# TMC2210_V10.net
KiCad netlist of a schematic drawn in Altium Designer
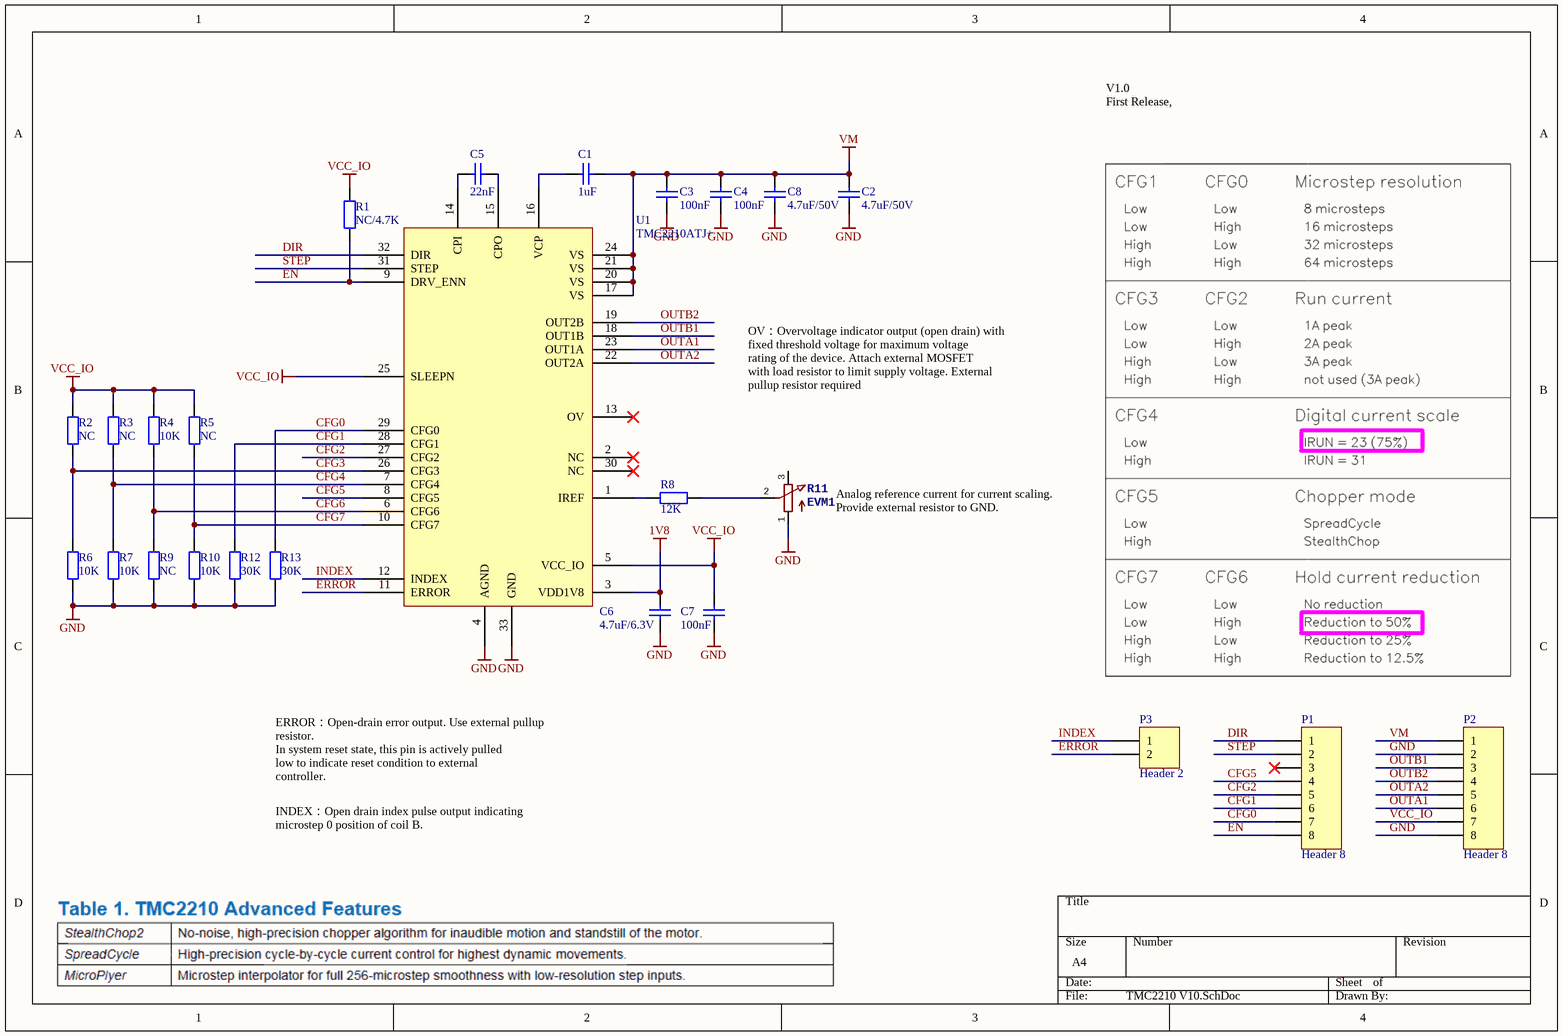
[diagram p0: TMC2210 V10.SchDoc]

(export (version "E")
  (design (tool "Eeschema 10.0.6"))
  (components
    (comp (ref "C1") (value "1uF") (footprint "CAP0402_NS") (libsource (lib "接插件库") (part "Capacitor")))
    (comp (ref "C2") (value "4.7uF/50V") (footprint "CAP0805") (libsource (lib "接插件库") (part "Capacitor")))
    (comp (ref "C3") (value "100nF") (footprint "CAP0402_NS") (libsource (lib "接插件库") (part "Capacitor")))
    (comp (ref "C4") (value "100nF") (footprint "CAP0402_NS") (libsource (lib "接插件库") (part "Capacitor")))
    (comp (ref "C5") (value "22nF") (footprint "CAP0402_NS") (libsource (lib "接插件库") (part "Capacitor")))
    (comp (ref "C6")
      (value "4.7uF/6.3V")
      (footprint "CAP0402_NS")
      (libsource (lib "接插件库") (part "Capacitor"))
    )
    (comp (ref "C7") (value "100nF") (footprint "CAP0402_NS") (libsource (lib "接插件库") (part "Capacitor")))
    (comp (ref "C8") (value "4.7uF/50V") (footprint "CAP0805") (libsource (lib "接插件库") (part "Capacitor")))
    (comp (ref "P1")
      (value "Header 8")
      (footprint "Header 1X8")
      (description "Header, 8-Pin")
      (fields (field (name "PUBLISHER") "Altium Limited"))
      (libsource (lib "Miscellaneous Connectors") (part "Header 8"))
    )
    (comp (ref "P2")
      (value "Header 8")
      (footprint "Header 1X8")
      (description "Header, 8-Pin")
      (fields (field (name "PUBLISHER") "Altium Limited"))
      (libsource (lib "Miscellaneous Connectors") (part "Header 8"))
    )
    (comp (ref "P3")
      (value "Header 2")
      (footprint "HDR1X2")
      (description "Header, 2-Pin")
      (fields (field (name "PUBLISHER") "Altium Limited"))
      (libsource (lib "Miscellaneous Connectors") (part "Header 2"))
    )
    (comp (ref "R1") (value "NC/4.7K") (footprint "RES0402_NS") (libsource (lib "接插件库") (part "Resistor")))
    (comp (ref "R2") (value "NC") (footprint "RES0402_NS") (libsource (lib "接插件库") (part "Resistor")))
    (comp (ref "R3") (value "NC") (footprint "RES0402_NS") (libsource (lib "接插件库") (part "Resistor")))
    (comp (ref "R4") (value "10K") (footprint "RES0402_NS") (libsource (lib "接插件库") (part "Resistor")))
    (comp (ref "R5") (value "NC") (footprint "RES0402_NS") (libsource (lib "接插件库") (part "Resistor")))
    (comp (ref "R6") (value "10K") (footprint "RES0402_NS") (libsource (lib "接插件库") (part "Resistor")))
    (comp (ref "R7") (value "10K") (footprint "RES0402_NS") (libsource (lib "接插件库") (part "Resistor")))
    (comp (ref "R8") (value "12K") (footprint "RES0402") (libsource (lib "") (part "Resistor_1")))
    (comp (ref "R9") (value "NC") (footprint "RES0402_NS") (libsource (lib "接插件库") (part "Resistor")))
    (comp (ref "R10") (value "10K") (footprint "RES0402_NS") (libsource (lib "接插件库") (part "Resistor")))
    (comp (ref "R11")
      (value "EVM1USX30B54")
      (footprint "POT_EVM3R")
      (description "Potentiometer")
      (libsource (lib "we-rcl") (part "POTEVM3R"))
    )
    (comp (ref "R12") (value "30K") (footprint "RES0402_NS") (libsource (lib "接插件库") (part "Resistor")))
    (comp (ref "R13") (value "30K") (footprint "RES0402_NS") (libsource (lib "接插件库") (part "Resistor")))
    (comp (ref "U1")
      (value "TMC2210ATJ+")
      (footprint "QFN32(Atmel)")
      (libsource (lib "接插件库") (part "TMC2210ATJ+"))
    )
  )
  (nets
    (net (code "1") (name "/CFG0") (class "Default")
      (node (ref "P1") (pin "7") (pinfunction "7_7") (pintype "passive"))
      (node (ref "R13") (pin "2") (pinfunction "2_2") (pintype "passive"))
      (node (ref "U1") (pin "29") (pinfunction "CFG0_29") (pintype "passive"))
    )
    (net (code "2") (name "/CFG1") (class "Default")
      (node (ref "P1") (pin "6") (pinfunction "6_6") (pintype "passive"))
      (node (ref "R12") (pin "2") (pinfunction "2_2") (pintype "passive"))
      (node (ref "U1") (pin "28") (pinfunction "CFG1_28") (pintype "passive"))
    )
    (net (code "3") (name "/CFG2") (class "Default")
      (node (ref "P1") (pin "5") (pinfunction "5_5") (pintype "passive"))
      (node (ref "U1") (pin "27") (pinfunction "CFG2_27") (pintype "passive"))
    )
    (net (code "4") (name "/CFG3") (class "Default")
      (node (ref "R2") (pin "1") (pinfunction "1_1") (pintype "passive"))
      (node (ref "R6") (pin "2") (pinfunction "2_2") (pintype "passive"))
      (node (ref "U1") (pin "26") (pinfunction "CFG3_26") (pintype "passive"))
    )
    (net (code "5") (name "/CFG4") (class "Default")
      (node (ref "R3") (pin "1") (pinfunction "1_1") (pintype "passive"))
      (node (ref "R7") (pin "2") (pinfunction "2_2") (pintype "passive"))
      (node (ref "U1") (pin "7") (pinfunction "CFG4_7") (pintype "passive"))
    )
    (net (code "6") (name "/CFG5") (class "Default")
      (node (ref "P1") (pin "4") (pinfunction "4_4") (pintype "passive"))
      (node (ref "U1") (pin "8") (pinfunction "CFG5_8") (pintype "passive"))
    )
    (net (code "7") (name "/CFG6") (class "Default")
      (node (ref "R4") (pin "1") (pinfunction "1_1") (pintype "passive"))
      (node (ref "R9") (pin "2") (pinfunction "2_2") (pintype "passive"))
      (node (ref "U1") (pin "6") (pinfunction "CFG6_6") (pintype "passive"))
    )
    (net (code "8") (name "/CFG7") (class "Default")
      (node (ref "R10") (pin "2") (pinfunction "2_2") (pintype "passive"))
      (node (ref "R5") (pin "1") (pinfunction "1_1") (pintype "passive"))
      (node (ref "U1") (pin "10") (pinfunction "CFG7_10") (pintype "passive"))
    )
    (net (code "9") (name "/DIR") (class "Default")
      (node (ref "P1") (pin "1") (pinfunction "1_1") (pintype "passive"))
      (node (ref "U1") (pin "32") (pinfunction "DIR_32") (pintype "passive"))
    )
    (net (code "10") (name "/EN") (class "Default")
      (node (ref "P1") (pin "8") (pinfunction "8_8") (pintype "passive"))
      (node (ref "R1") (pin "1") (pinfunction "1_1") (pintype "passive"))
      (node (ref "U1") (pin "9") (pinfunction "DRV_ENN_9") (pintype "passive"))
    )
    (net (code "11") (name "/ERROR") (class "Default")
      (node (ref "P3") (pin "2") (pinfunction "2_2") (pintype "passive"))
      (node (ref "U1") (pin "11") (pinfunction "ERROR_11") (pintype "passive"))
    )
    (net (code "12") (name "/INDEX") (class "Default")
      (node (ref "P3") (pin "1") (pinfunction "1_1") (pintype "passive"))
      (node (ref "U1") (pin "12") (pinfunction "INDEX_12") (pintype "passive"))
    )
    (net (code "13") (name "/OUTA1") (class "Default")
      (node (ref "P2") (pin "6") (pinfunction "6_6") (pintype "passive"))
      (node (ref "U1") (pin "23") (pinfunction "OUT1A_23") (pintype "passive"))
    )
    (net (code "14") (name "/OUTA2") (class "Default")
      (node (ref "P2") (pin "5") (pinfunction "5_5") (pintype "passive"))
      (node (ref "U1") (pin "22") (pinfunction "OUT2A_22") (pintype "passive"))
    )
    (net (code "15") (name "/OUTB1") (class "Default")
      (node (ref "P2") (pin "3") (pinfunction "3_3") (pintype "passive"))
      (node (ref "U1") (pin "18") (pinfunction "OUT1B_18") (pintype "passive"))
    )
    (net (code "16") (name "/OUTB2") (class "Default")
      (node (ref "P2") (pin "4") (pinfunction "4_4") (pintype "passive"))
      (node (ref "U1") (pin "19") (pinfunction "OUT2B_19") (pintype "passive"))
    )
    (net (code "17") (name "/STEP") (class "Default")
      (node (ref "P1") (pin "2") (pinfunction "2_2") (pintype "passive"))
      (node (ref "U1") (pin "31") (pinfunction "STEP_31") (pintype "passive"))
    )
    (net (code "18") (name "1V8") (class "Default")
      (node (ref "C6") (pin "1") (pinfunction "1_1") (pintype "passive"))
      (node (ref "U1") (pin "3") (pinfunction "VDD1V8_3") (pintype "passive"))
    )
    (net (code "19") (name "GND") (class "Default")
      (node (ref "C2") (pin "1") (pinfunction "1_1") (pintype "passive"))
      (node (ref "C3") (pin "1") (pinfunction "1_1") (pintype "passive"))
      (node (ref "C4") (pin "1") (pinfunction "1_1") (pintype "passive"))
      (node (ref "C6") (pin "2") (pinfunction "2_2") (pintype "passive"))
      (node (ref "C7") (pin "2") (pinfunction "2_2") (pintype "passive"))
      (node (ref "C8") (pin "1") (pinfunction "1_1") (pintype "passive"))
      (node (ref "P2") (pin "2") (pinfunction "2_2") (pintype "passive"))
      (node (ref "P2") (pin "8") (pinfunction "8_8") (pintype "passive"))
      (node (ref "R10") (pin "1") (pinfunction "1_1") (pintype "passive"))
      (node (ref "R11") (pin "1") (pinfunction "A_1") (pintype "passive"))
      (node (ref "R12") (pin "1") (pinfunction "1_1") (pintype "passive"))
      (node (ref "R13") (pin "1") (pinfunction "1_1") (pintype "passive"))
      (node (ref "R6") (pin "1") (pinfunction "1_1") (pintype "passive"))
      (node (ref "R7") (pin "1") (pinfunction "1_1") (pintype "passive"))
      (node (ref "R9") (pin "1") (pinfunction "1_1") (pintype "passive"))
      (node (ref "U1") (pin "33") (pinfunction "GND_33") (pintype "passive"))
      (node (ref "U1") (pin "4") (pinfunction "AGND_4") (pintype "passive"))
    )
    (net (code "20") (name "Net-(R11-S)") (class "Default")
      (node (ref "R11") (pin "2") (pinfunction "S_2") (pintype "passive"))
      (node (ref "R8") (pin "1") (pinfunction "1_1") (pintype "passive"))
    )
    (net (code "21") (name "Net-(U1-CPI)") (class "Default")
      (node (ref "C5") (pin "1") (pinfunction "1_1") (pintype "passive"))
      (node (ref "U1") (pin "14") (pinfunction "CPI_14") (pintype "passive"))
    )
    (net (code "22") (name "Net-(U1-CPO)") (class "Default")
      (node (ref "C5") (pin "2") (pinfunction "2_2") (pintype "passive"))
      (node (ref "U1") (pin "15") (pinfunction "CPO_15") (pintype "passive"))
    )
    (net (code "23") (name "Net-(U1-IREF)") (class "Default")
      (node (ref "R8") (pin "2") (pinfunction "2_2") (pintype "passive"))
      (node (ref "U1") (pin "1") (pinfunction "IREF_1") (pintype "passive"))
    )
    (net (code "24") (name "Net-(U1-VCP)") (class "Default")
      (node (ref "C1") (pin "1") (pinfunction "1_1") (pintype "passive"))
      (node (ref "U1") (pin "16") (pinfunction "VCP_16") (pintype "passive"))
    )
    (net (code "25") (name "VCC_IO") (class "Default")
      (node (ref "C7") (pin "1") (pinfunction "1_1") (pintype "passive"))
      (node (ref "P2") (pin "7") (pinfunction "7_7") (pintype "passive"))
      (node (ref "R1") (pin "2") (pinfunction "2_2") (pintype "passive"))
      (node (ref "R2") (pin "2") (pinfunction "2_2") (pintype "passive"))
      (node (ref "R3") (pin "2") (pinfunction "2_2") (pintype "passive"))
      (node (ref "R4") (pin "2") (pinfunction "2_2") (pintype "passive"))
      (node (ref "R5") (pin "2") (pinfunction "2_2") (pintype "passive"))
      (node (ref "U1") (pin "25") (pinfunction "SLEEPN_25") (pintype "passive"))
      (node (ref "U1") (pin "5") (pinfunction "VCC_IO_5") (pintype "passive"))
    )
    (net (code "26") (name "VM") (class "Default")
      (node (ref "C1") (pin "2") (pinfunction "2_2") (pintype "passive"))
      (node (ref "C2") (pin "2") (pinfunction "2_2") (pintype "passive"))
      (node (ref "C3") (pin "2") (pinfunction "2_2") (pintype "passive"))
      (node (ref "C4") (pin "2") (pinfunction "2_2") (pintype "passive"))
      (node (ref "C8") (pin "2") (pinfunction "2_2") (pintype "passive"))
      (node (ref "P2") (pin "1") (pinfunction "1_1") (pintype "passive"))
      (node (ref "U1") (pin "17") (pinfunction "VS_17") (pintype "passive"))
      (node (ref "U1") (pin "20") (pinfunction "VS_20") (pintype "passive"))
      (node (ref "U1") (pin "21") (pinfunction "VS_21") (pintype "passive"))
      (node (ref "U1") (pin "24") (pinfunction "VS_24") (pintype "passive"))
    )
    (net (code "27") (name "unconnected-(P1-Pad3)") (class "Default")
      (node (ref "P1") (pin "3") (pinfunction "3_3") (pintype "passive+no_connect"))
    )
    (net (code "28") (name "unconnected-(R11-E-Pad3)") (class "Default")
      (node (ref "R11") (pin "3") (pinfunction "E_3") (pintype "passive"))
    )
    (net (code "29") (name "unconnected-(U1-NC-Pad2)") (class "Default")
      (node (ref "U1") (pin "2") (pinfunction "NC_2") (pintype "passive+no_connect"))
    )
    (net (code "30") (name "unconnected-(U1-NC-Pad30)") (class "Default")
      (node (ref "U1") (pin "30") (pinfunction "NC_30") (pintype "passive+no_connect"))
    )
    (net (code "31") (name "unconnected-(U1-OV-Pad13)") (class "Default")
      (node (ref "U1") (pin "13") (pinfunction "OV_13") (pintype "passive+no_connect"))
    )
  )
)
